# driver.net
KiCad netlist of a schematic drawn in EAGLE
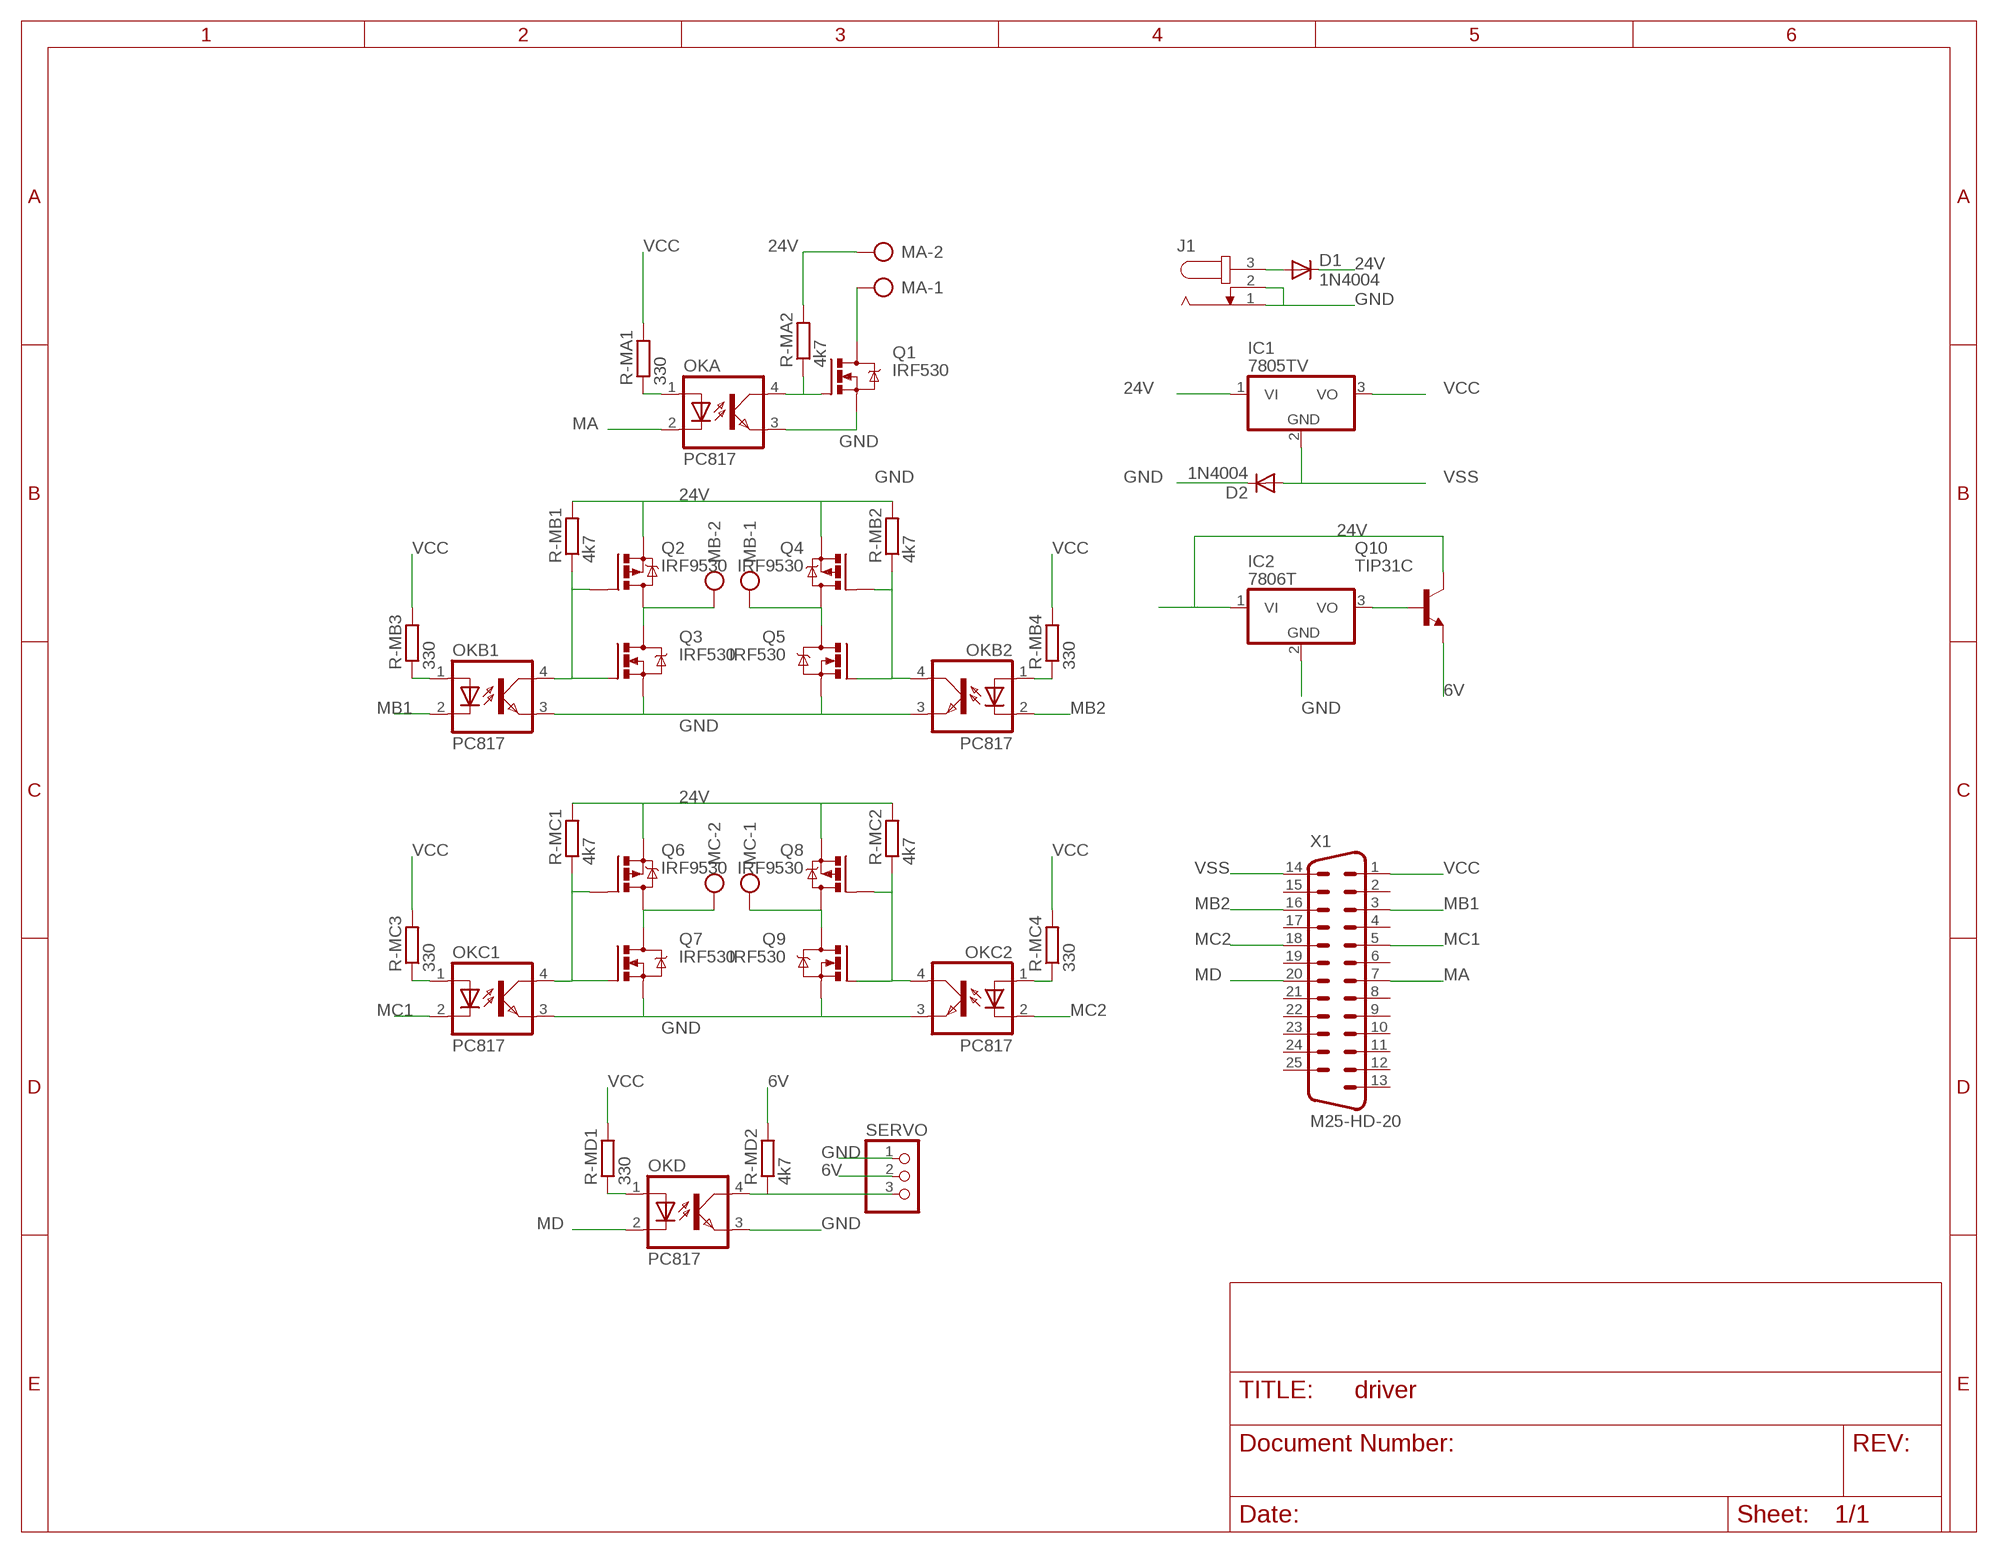
[diagram p0: schematic, sheet 1]

(export (version "E")
  (design (tool "Eeschema 10.0.6"))
  (components
    (comp (ref "D1")
      (value "1N4004")
      (footprint "eagle-import:DO41-10")
      (libsource (lib "eagle-import") (part "1N4004"))
    )
    (comp (ref "D2")
      (value "1N4004")
      (footprint "eagle-import:DO41-10")
      (libsource (lib "eagle-import") (part "1N4004"))
    )
    (comp (ref "IC1")
      (value "7805TV")
      (footprint "eagle-import:TO220V")
      (libsource (lib "eagle-import") (part "78TV05"))
    )
    (comp (ref "IC2")
      (value "7806T")
      (footprint "eagle-import:TO220H")
      (libsource (lib "eagle-import") (part "78T06"))
    )
    (comp (ref "J1")
      (value "JACK-PLUG0")
      (footprint "eagle-import:SPC4077")
      (libsource (lib "eagle-import") (part "JACK-PLUG0"))
    )
    (comp (ref "MA")
      (value "AK500/2")
      (footprint "eagle-import:AK500_2")
      (libsource (lib "eagle-import") (part "AK500/2"))
    )
    (comp (ref "MB")
      (value "AK500/2")
      (footprint "eagle-import:AK500_2")
      (libsource (lib "eagle-import") (part "AK500/2"))
    )
    (comp (ref "MC")
      (value "AK500/2")
      (footprint "eagle-import:AK500_2")
      (libsource (lib "eagle-import") (part "AK500/2"))
    )
    (comp (ref "OKA")
      (value "PC817")
      (footprint "eagle-import:DIL04")
      (fields (field (name "MPN") "PC817X4J000F"))
      (libsource (lib "eagle-import") (part "PC817"))
    )
    (comp (ref "OKB1")
      (value "PC817")
      (footprint "eagle-import:DIL04")
      (fields (field (name "MPN") "PC817X4J000F"))
      (libsource (lib "eagle-import") (part "PC817"))
    )
    (comp (ref "OKB2")
      (value "PC817")
      (footprint "eagle-import:DIL04")
      (fields (field (name "MPN") "PC817X4J000F"))
      (libsource (lib "eagle-import") (part "PC817"))
    )
    (comp (ref "OKC1")
      (value "PC817")
      (footprint "eagle-import:DIL04")
      (fields (field (name "MPN") "PC817X4J000F"))
      (libsource (lib "eagle-import") (part "PC817"))
    )
    (comp (ref "OKC2")
      (value "PC817")
      (footprint "eagle-import:DIL04")
      (fields (field (name "MPN") "PC817X4J000F"))
      (libsource (lib "eagle-import") (part "PC817"))
    )
    (comp (ref "OKD")
      (value "PC817")
      (footprint "eagle-import:DIL04")
      (fields (field (name "MPN") "PC817X4J000F"))
      (libsource (lib "eagle-import") (part "PC817"))
    )
    (comp (ref "Q1")
      (value "IRF530")
      (footprint "eagle-import:TO220BV")
      (libsource (lib "eagle-import") (part "IRF530"))
    )
    (comp (ref "Q2")
      (value "IRF9530")
      (footprint "eagle-import:TO220BV")
      (libsource (lib "eagle-import") (part "IRF9530"))
    )
    (comp (ref "Q3")
      (value "IRF530")
      (footprint "eagle-import:TO220BV")
      (libsource (lib "eagle-import") (part "IRF530"))
    )
    (comp (ref "Q4")
      (value "IRF9530")
      (footprint "eagle-import:TO220BV")
      (libsource (lib "eagle-import") (part "IRF9530"))
    )
    (comp (ref "Q5")
      (value "IRF530")
      (footprint "eagle-import:TO220BV")
      (libsource (lib "eagle-import") (part "IRF530"))
    )
    (comp (ref "Q6")
      (value "IRF9530")
      (footprint "eagle-import:TO220BV")
      (libsource (lib "eagle-import") (part "IRF9530"))
    )
    (comp (ref "Q7")
      (value "IRF530")
      (footprint "eagle-import:TO220BV")
      (libsource (lib "eagle-import") (part "IRF530"))
    )
    (comp (ref "Q8")
      (value "IRF9530")
      (footprint "eagle-import:TO220BV")
      (libsource (lib "eagle-import") (part "IRF9530"))
    )
    (comp (ref "Q9")
      (value "IRF530")
      (footprint "eagle-import:TO220BV")
      (libsource (lib "eagle-import") (part "IRF530"))
    )
    (comp (ref "Q10")
      (value "TIP31C")
      (footprint "eagle-import:TO220")
      (libsource (lib "eagle-import") (part "TIP31C"))
    )
    (comp (ref "R-MA1")
      (value "330")
      (footprint "eagle-import:0204_7")
      (libsource (lib "eagle-import") (part "R-EU_0204/7"))
    )
    (comp (ref "R-MA2")
      (value "4k7")
      (footprint "eagle-import:0204_7")
      (libsource (lib "eagle-import") (part "R-EU_0204/7"))
    )
    (comp (ref "R-MB1")
      (value "4k7")
      (footprint "eagle-import:0204_7")
      (libsource (lib "eagle-import") (part "R-EU_0204/7"))
    )
    (comp (ref "R-MB2")
      (value "4k7")
      (footprint "eagle-import:0204_7")
      (libsource (lib "eagle-import") (part "R-EU_0204/7"))
    )
    (comp (ref "R-MB3")
      (value "330")
      (footprint "eagle-import:0204_7")
      (libsource (lib "eagle-import") (part "R-EU_0204/7"))
    )
    (comp (ref "R-MB4")
      (value "330")
      (footprint "eagle-import:0204_7")
      (libsource (lib "eagle-import") (part "R-EU_0204/7"))
    )
    (comp (ref "R-MC1")
      (value "4k7")
      (footprint "eagle-import:0204_7")
      (libsource (lib "eagle-import") (part "R-EU_0204/7"))
    )
    (comp (ref "R-MC2")
      (value "4k7")
      (footprint "eagle-import:0204_7")
      (libsource (lib "eagle-import") (part "R-EU_0204/7"))
    )
    (comp (ref "R-MC3")
      (value "330")
      (footprint "eagle-import:0204_7")
      (libsource (lib "eagle-import") (part "R-EU_0204/7"))
    )
    (comp (ref "R-MC4")
      (value "330")
      (footprint "eagle-import:0204_7")
      (libsource (lib "eagle-import") (part "R-EU_0204/7"))
    )
    (comp (ref "R-MD1")
      (value "330")
      (footprint "eagle-import:0204_7")
      (libsource (lib "eagle-import") (part "R-EU_0204/7"))
    )
    (comp (ref "R-MD2")
      (value "4k7")
      (footprint "eagle-import:0204_7")
      (libsource (lib "eagle-import") (part "R-EU_0204/7"))
    )
    (comp (ref "SERVO")
      (value "PINHD-1X3")
      (footprint "eagle-import:1X03")
      (libsource (lib "eagle-import") (part "PINHD-1X3"))
    )
    (comp (ref "X1")
      (value "M25-HD-20")
      (footprint "eagle-import:M25-HD-20")
      (libsource (lib "eagle-import") (part "M25-HD-20"))
    )
  )
  (nets
    (net (code "1") (name "/6V") (class "Default")
      (node (ref "Q10") (pin "3") (pinfunction "E_3") (pintype "passive"))
      (node (ref "R-MD2") (pin "2") (pinfunction "2_2") (pintype "passive"))
      (node (ref "SERVO") (pin "2") (pinfunction "2_2") (pintype "passive"))
    )
    (net (code "2") (name "/24V") (class "Default")
      (node (ref "D1") (pin "C") (pinfunction "C_C") (pintype "passive"))
      (node (ref "IC1") (pin "1") (pinfunction "VI_1") (pintype "input"))
      (node (ref "IC2") (pin "1") (pinfunction "VI_1") (pintype "input"))
      (node (ref "MA") (pin "2") (pinfunction "KL_2") (pintype "passive"))
      (node (ref "Q10") (pin "2") (pinfunction "C_2") (pintype "passive"))
      (node (ref "Q2") (pin "S") (pinfunction "S_S") (pintype "passive"))
      (node (ref "Q4") (pin "S") (pinfunction "S_S") (pintype "passive"))
      (node (ref "Q6") (pin "S") (pinfunction "S_S") (pintype "passive"))
      (node (ref "Q8") (pin "S") (pinfunction "S_S") (pintype "passive"))
      (node (ref "R-MA2") (pin "2") (pinfunction "2_2") (pintype "passive"))
      (node (ref "R-MB1") (pin "2") (pinfunction "2_2") (pintype "passive"))
      (node (ref "R-MB2") (pin "2") (pinfunction "2_2") (pintype "passive"))
      (node (ref "R-MC1") (pin "2") (pinfunction "2_2") (pintype "passive"))
      (node (ref "R-MC2") (pin "2") (pinfunction "2_2") (pintype "passive"))
    )
    (net (code "3") (name "/GND") (class "Default")
      (node (ref "D2") (pin "C") (pinfunction "C_C") (pintype "passive"))
      (node (ref "IC2") (pin "2") (pinfunction "GND_2") (pintype "passive"))
      (node (ref "J1") (pin "1") (pinfunction "1_1") (pintype "passive"))
      (node (ref "J1") (pin "2") (pinfunction "2_2") (pintype "passive"))
      (node (ref "OKA") (pin "3") (pinfunction "EMIT_3") (pintype "passive"))
      (node (ref "OKB1") (pin "3") (pinfunction "EMIT_3") (pintype "passive"))
      (node (ref "OKB2") (pin "3") (pinfunction "EMIT_3") (pintype "passive"))
      (node (ref "OKC1") (pin "3") (pinfunction "EMIT_3") (pintype "passive"))
      (node (ref "OKC2") (pin "3") (pinfunction "EMIT_3") (pintype "passive"))
      (node (ref "OKD") (pin "3") (pinfunction "EMIT_3") (pintype "passive"))
      (node (ref "Q1") (pin "S") (pinfunction "S_S") (pintype "passive"))
      (node (ref "Q3") (pin "S") (pinfunction "S_S") (pintype "passive"))
      (node (ref "Q5") (pin "S") (pinfunction "S_S") (pintype "passive"))
      (node (ref "Q7") (pin "S") (pinfunction "S_S") (pintype "passive"))
      (node (ref "Q9") (pin "S") (pinfunction "S_S") (pintype "passive"))
      (node (ref "SERVO") (pin "1") (pinfunction "1_1") (pintype "passive"))
    )
    (net (code "4") (name "/MA") (class "Default")
      (node (ref "OKA") (pin "2") (pinfunction "C_2") (pintype "passive"))
      (node (ref "X1") (pin "7") (pinfunction "7_7") (pintype "passive"))
    )
    (net (code "5") (name "/MB1") (class "Default")
      (node (ref "OKB1") (pin "2") (pinfunction "C_2") (pintype "passive"))
      (node (ref "X1") (pin "3") (pinfunction "3_3") (pintype "passive"))
    )
    (net (code "6") (name "/MB2") (class "Default")
      (node (ref "OKB2") (pin "2") (pinfunction "C_2") (pintype "passive"))
      (node (ref "X1") (pin "16") (pinfunction "16_16") (pintype "passive"))
    )
    (net (code "7") (name "/MC1") (class "Default")
      (node (ref "OKC1") (pin "2") (pinfunction "C_2") (pintype "passive"))
      (node (ref "X1") (pin "5") (pinfunction "5_5") (pintype "passive"))
    )
    (net (code "8") (name "/MC2") (class "Default")
      (node (ref "OKC2") (pin "2") (pinfunction "C_2") (pintype "passive"))
      (node (ref "X1") (pin "18") (pinfunction "18_18") (pintype "passive"))
    )
    (net (code "9") (name "/MD") (class "Default")
      (node (ref "OKD") (pin "2") (pinfunction "C_2") (pintype "passive"))
      (node (ref "X1") (pin "20") (pinfunction "20_20") (pintype "passive"))
    )
    (net (code "10") (name "/VCC") (class "Default")
      (node (ref "IC1") (pin "3") (pinfunction "VO_3") (pintype "passive"))
      (node (ref "R-MA1") (pin "2") (pinfunction "2_2") (pintype "passive"))
      (node (ref "R-MB3") (pin "2") (pinfunction "2_2") (pintype "passive"))
      (node (ref "R-MB4") (pin "2") (pinfunction "2_2") (pintype "passive"))
      (node (ref "R-MC3") (pin "2") (pinfunction "2_2") (pintype "passive"))
      (node (ref "R-MC4") (pin "2") (pinfunction "2_2") (pintype "passive"))
      (node (ref "R-MD1") (pin "2") (pinfunction "2_2") (pintype "passive"))
      (node (ref "X1") (pin "1") (pinfunction "1_1") (pintype "passive"))
    )
    (net (code "11") (name "/VSS") (class "Default")
      (node (ref "D2") (pin "A") (pinfunction "A_A") (pintype "passive"))
      (node (ref "IC1") (pin "2") (pinfunction "GND_2") (pintype "passive"))
      (node (ref "X1") (pin "14") (pinfunction "14_14") (pintype "passive"))
    )
    (net (code "12") (name "Net-(D1-PadA)") (class "Default")
      (node (ref "D1") (pin "A") (pinfunction "A_A") (pintype "passive"))
      (node (ref "J1") (pin "3") (pinfunction "3_3") (pintype "passive"))
    )
    (net (code "13") (name "Net-(IC2-VO)") (class "Default")
      (node (ref "IC2") (pin "3") (pinfunction "VO_3") (pintype "passive"))
      (node (ref "Q10") (pin "1") (pinfunction "B_1") (pintype "passive"))
    )
    (net (code "14") (name "Net-(MAA-KL)") (class "Default")
      (node (ref "MA") (pin "1") (pinfunction "KL_1") (pintype "passive"))
      (node (ref "Q1") (pin "D") (pinfunction "D_D") (pintype "passive"))
    )
    (net (code "15") (name "Net-(MBA-KL)") (class "Default")
      (node (ref "MB") (pin "1") (pinfunction "KL_1") (pintype "passive"))
      (node (ref "Q4") (pin "D") (pinfunction "D_D") (pintype "passive"))
      (node (ref "Q5") (pin "D") (pinfunction "D_D") (pintype "passive"))
    )
    (net (code "16") (name "Net-(MBB-KL)") (class "Default")
      (node (ref "MB") (pin "2") (pinfunction "KL_2") (pintype "passive"))
      (node (ref "Q2") (pin "D") (pinfunction "D_D") (pintype "passive"))
      (node (ref "Q3") (pin "D") (pinfunction "D_D") (pintype "passive"))
    )
    (net (code "17") (name "Net-(MCA-KL)") (class "Default")
      (node (ref "MC") (pin "1") (pinfunction "KL_1") (pintype "passive"))
      (node (ref "Q8") (pin "D") (pinfunction "D_D") (pintype "passive"))
      (node (ref "Q9") (pin "D") (pinfunction "D_D") (pintype "passive"))
    )
    (net (code "18") (name "Net-(MCB-KL)") (class "Default")
      (node (ref "MC") (pin "2") (pinfunction "KL_2") (pintype "passive"))
      (node (ref "Q6") (pin "D") (pinfunction "D_D") (pintype "passive"))
      (node (ref "Q7") (pin "D") (pinfunction "D_D") (pintype "passive"))
    )
    (net (code "19") (name "Net-(OKA-A)") (class "Default")
      (node (ref "OKA") (pin "1") (pinfunction "A_1") (pintype "passive"))
      (node (ref "R-MA1") (pin "1") (pinfunction "1_1") (pintype "passive"))
    )
    (net (code "20") (name "Net-(OKA-COL)") (class "Default")
      (node (ref "OKA") (pin "4") (pinfunction "COL_4") (pintype "passive"))
      (node (ref "Q1") (pin "G") (pinfunction "G_G") (pintype "passive"))
      (node (ref "R-MA2") (pin "1") (pinfunction "1_1") (pintype "passive"))
    )
    (net (code "21") (name "Net-(OKB1-A)") (class "Default")
      (node (ref "OKB1") (pin "1") (pinfunction "A_1") (pintype "passive"))
      (node (ref "R-MB3") (pin "1") (pinfunction "1_1") (pintype "passive"))
    )
    (net (code "22") (name "Net-(OKB1-COL)") (class "Default")
      (node (ref "OKB1") (pin "4") (pinfunction "COL_4") (pintype "passive"))
      (node (ref "Q2") (pin "G") (pinfunction "G_G") (pintype "passive"))
      (node (ref "Q3") (pin "G") (pinfunction "G_G") (pintype "passive"))
      (node (ref "R-MB1") (pin "1") (pinfunction "1_1") (pintype "passive"))
    )
    (net (code "23") (name "Net-(OKB2-A)") (class "Default")
      (node (ref "OKB2") (pin "1") (pinfunction "A_1") (pintype "passive"))
      (node (ref "R-MB4") (pin "1") (pinfunction "1_1") (pintype "passive"))
    )
    (net (code "24") (name "Net-(OKB2-COL)") (class "Default")
      (node (ref "OKB2") (pin "4") (pinfunction "COL_4") (pintype "passive"))
      (node (ref "Q4") (pin "G") (pinfunction "G_G") (pintype "passive"))
      (node (ref "Q5") (pin "G") (pinfunction "G_G") (pintype "passive"))
      (node (ref "R-MB2") (pin "1") (pinfunction "1_1") (pintype "passive"))
    )
    (net (code "25") (name "Net-(OKC1-A)") (class "Default")
      (node (ref "OKC1") (pin "1") (pinfunction "A_1") (pintype "passive"))
      (node (ref "R-MC3") (pin "1") (pinfunction "1_1") (pintype "passive"))
    )
    (net (code "26") (name "Net-(OKC1-COL)") (class "Default")
      (node (ref "OKC1") (pin "4") (pinfunction "COL_4") (pintype "passive"))
      (node (ref "Q6") (pin "G") (pinfunction "G_G") (pintype "passive"))
      (node (ref "Q7") (pin "G") (pinfunction "G_G") (pintype "passive"))
      (node (ref "R-MC1") (pin "1") (pinfunction "1_1") (pintype "passive"))
    )
    (net (code "27") (name "Net-(OKC2-A)") (class "Default")
      (node (ref "OKC2") (pin "1") (pinfunction "A_1") (pintype "passive"))
      (node (ref "R-MC4") (pin "1") (pinfunction "1_1") (pintype "passive"))
    )
    (net (code "28") (name "Net-(OKC2-COL)") (class "Default")
      (node (ref "OKC2") (pin "4") (pinfunction "COL_4") (pintype "passive"))
      (node (ref "Q8") (pin "G") (pinfunction "G_G") (pintype "passive"))
      (node (ref "Q9") (pin "G") (pinfunction "G_G") (pintype "passive"))
      (node (ref "R-MC2") (pin "1") (pinfunction "1_1") (pintype "passive"))
    )
    (net (code "29") (name "Net-(OKD-A)") (class "Default")
      (node (ref "OKD") (pin "1") (pinfunction "A_1") (pintype "passive"))
      (node (ref "R-MD1") (pin "1") (pinfunction "1_1") (pintype "passive"))
    )
    (net (code "30") (name "Net-(OKD-COL)") (class "Default")
      (node (ref "OKD") (pin "4") (pinfunction "COL_4") (pintype "passive"))
      (node (ref "R-MD2") (pin "1") (pinfunction "1_1") (pintype "passive"))
      (node (ref "SERVO") (pin "3") (pinfunction "3_3") (pintype "passive"))
    )
    (net (code "31") (name "unconnected-(X1-Pad2)") (class "Default")
      (node (ref "X1") (pin "2") (pinfunction "2_2") (pintype "passive"))
    )
    (net (code "32") (name "unconnected-(X1-Pad4)") (class "Default")
      (node (ref "X1") (pin "4") (pinfunction "4_4") (pintype "passive"))
    )
    (net (code "33") (name "unconnected-(X1-Pad6)") (class "Default")
      (node (ref "X1") (pin "6") (pinfunction "6_6") (pintype "passive"))
    )
    (net (code "34") (name "unconnected-(X1-Pad8)") (class "Default")
      (node (ref "X1") (pin "8") (pinfunction "8_8") (pintype "passive"))
    )
    (net (code "35") (name "unconnected-(X1-Pad9)") (class "Default")
      (node (ref "X1") (pin "9") (pinfunction "9_9") (pintype "passive"))
    )
    (net (code "36") (name "unconnected-(X1-Pad10)") (class "Default")
      (node (ref "X1") (pin "10") (pinfunction "10_10") (pintype "passive"))
    )
    (net (code "37") (name "unconnected-(X1-Pad11)") (class "Default")
      (node (ref "X1") (pin "11") (pinfunction "11_11") (pintype "passive"))
    )
    (net (code "38") (name "unconnected-(X1-Pad12)") (class "Default")
      (node (ref "X1") (pin "12") (pinfunction "12_12") (pintype "passive"))
    )
    (net (code "39") (name "unconnected-(X1-Pad13)") (class "Default")
      (node (ref "X1") (pin "13") (pinfunction "13_13") (pintype "passive"))
    )
    (net (code "40") (name "unconnected-(X1-Pad15)") (class "Default")
      (node (ref "X1") (pin "15") (pinfunction "15_15") (pintype "passive"))
    )
    (net (code "41") (name "unconnected-(X1-Pad17)") (class "Default")
      (node (ref "X1") (pin "17") (pinfunction "17_17") (pintype "passive"))
    )
    (net (code "42") (name "unconnected-(X1-Pad19)") (class "Default")
      (node (ref "X1") (pin "19") (pinfunction "19_19") (pintype "passive"))
    )
    (net (code "43") (name "unconnected-(X1-Pad21)") (class "Default")
      (node (ref "X1") (pin "21") (pinfunction "21_21") (pintype "passive"))
    )
    (net (code "44") (name "unconnected-(X1-Pad22)") (class "Default")
      (node (ref "X1") (pin "22") (pinfunction "22_22") (pintype "passive"))
    )
    (net (code "45") (name "unconnected-(X1-Pad23)") (class "Default")
      (node (ref "X1") (pin "23") (pinfunction "23_23") (pintype "passive"))
    )
    (net (code "46") (name "unconnected-(X1-Pad24)") (class "Default")
      (node (ref "X1") (pin "24") (pinfunction "24_24") (pintype "passive"))
    )
    (net (code "47") (name "unconnected-(X1-Pad25)") (class "Default")
      (node (ref "X1") (pin "25") (pinfunction "25_25") (pintype "passive"))
    )
  )
)
